# exp21ac.net
KiCad netlist of a schematic drawn in EAGLE
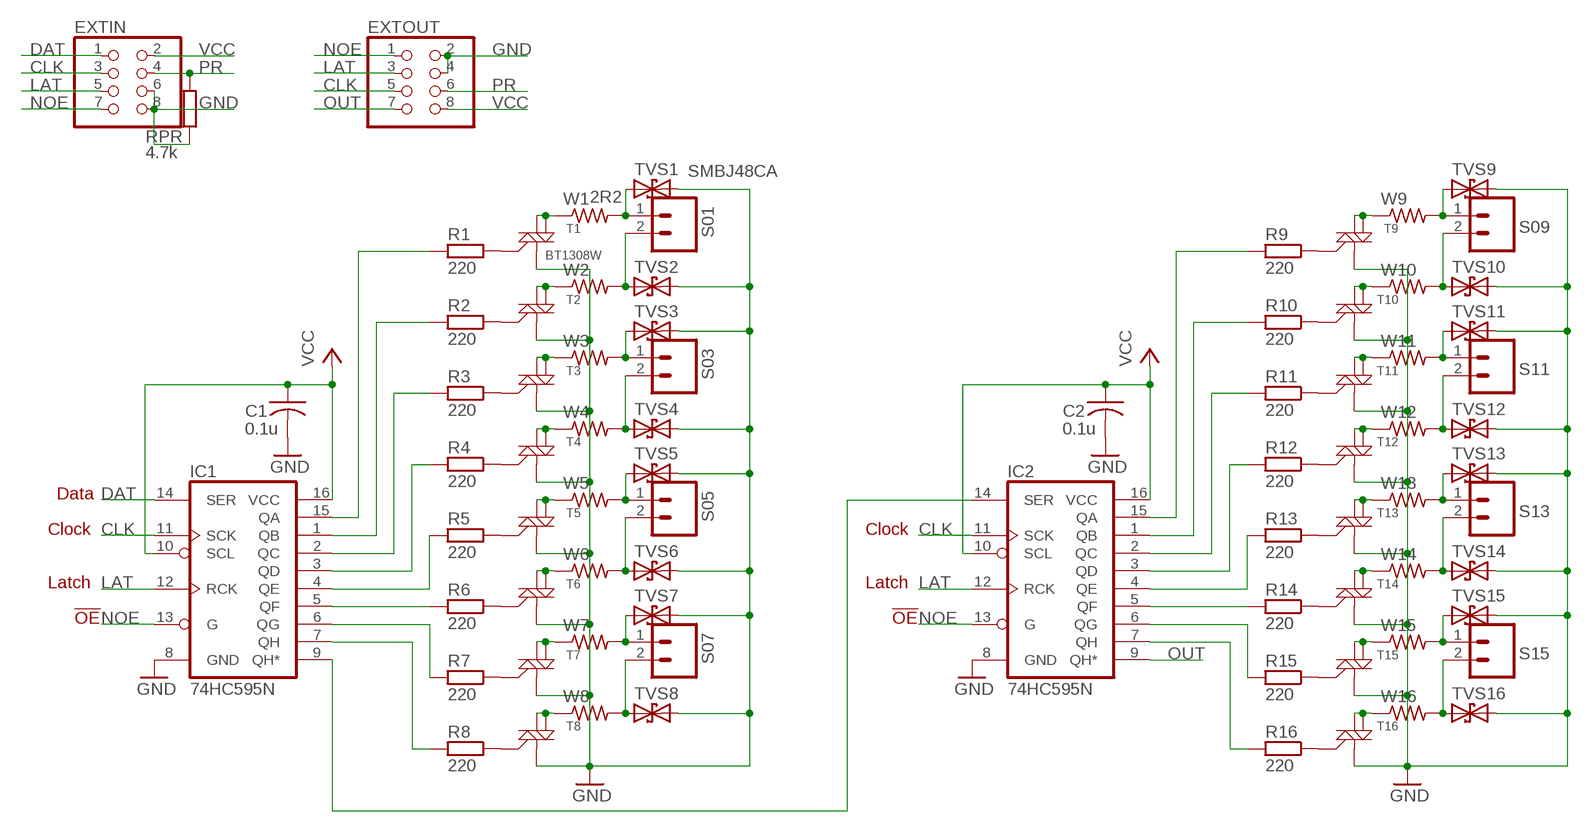
[diagram p0: schematic, sheet 1]

(export (version "E")
  (design (tool "Eeschema 10.0.6"))
  (components
    (comp (ref "C1")
      (value "0.1u")
      (footprint "eagle-import:C0603K")
      (libsource (lib "eagle-import") (part "C-USC0603K"))
    )
    (comp (ref "C2")
      (value "0.1u")
      (footprint "eagle-import:C0603K")
      (libsource (lib "eagle-import") (part "C-USC0603K"))
    )
    (comp (ref "EXTIN")
      (value "PINHD-2X4/90")
      (footprint "eagle-import:2X04_90")
      (libsource (lib "eagle-import") (part "PINHD-2X4/90"))
    )
    (comp (ref "EXTOUT")
      (value "PINHD-2X4/90")
      (footprint "eagle-import:2X04_90")
      (libsource (lib "eagle-import") (part "PINHD-2X4/90"))
    )
    (comp (ref "IC1")
      (value "74HC595N")
      (footprint "eagle-import:SO16")
      (libsource (lib "eagle-import") (part "74595DLS"))
    )
    (comp (ref "IC2")
      (value "74HC595N")
      (footprint "eagle-import:SO16")
      (libsource (lib "eagle-import") (part "74595DLS"))
    )
    (comp (ref "R1")
      (value "220")
      (footprint "eagle-import:R0603")
      (libsource (lib "eagle-import") (part "R-EU_R0603"))
    )
    (comp (ref "R2")
      (value "220")
      (footprint "eagle-import:R0603")
      (libsource (lib "eagle-import") (part "R-EU_R0603"))
    )
    (comp (ref "R3")
      (value "220")
      (footprint "eagle-import:R0603")
      (libsource (lib "eagle-import") (part "R-EU_R0603"))
    )
    (comp (ref "R4")
      (value "220")
      (footprint "eagle-import:R0603")
      (libsource (lib "eagle-import") (part "R-EU_R0603"))
    )
    (comp (ref "R5")
      (value "220")
      (footprint "eagle-import:R0603")
      (libsource (lib "eagle-import") (part "R-EU_R0603"))
    )
    (comp (ref "R6")
      (value "220")
      (footprint "eagle-import:R0603")
      (libsource (lib "eagle-import") (part "R-EU_R0603"))
    )
    (comp (ref "R7")
      (value "220")
      (footprint "eagle-import:R0603")
      (libsource (lib "eagle-import") (part "R-EU_R0603"))
    )
    (comp (ref "R8")
      (value "220")
      (footprint "eagle-import:R0603")
      (libsource (lib "eagle-import") (part "R-EU_R0603"))
    )
    (comp (ref "R9")
      (value "220")
      (footprint "eagle-import:R0603")
      (libsource (lib "eagle-import") (part "R-EU_R0603"))
    )
    (comp (ref "R10")
      (value "220")
      (footprint "eagle-import:R0603")
      (libsource (lib "eagle-import") (part "R-EU_R0603"))
    )
    (comp (ref "R11")
      (value "220")
      (footprint "eagle-import:R0603")
      (libsource (lib "eagle-import") (part "R-EU_R0603"))
    )
    (comp (ref "R12")
      (value "220")
      (footprint "eagle-import:R0603")
      (libsource (lib "eagle-import") (part "R-EU_R0603"))
    )
    (comp (ref "R13")
      (value "220")
      (footprint "eagle-import:R0603")
      (libsource (lib "eagle-import") (part "R-EU_R0603"))
    )
    (comp (ref "R14")
      (value "220")
      (footprint "eagle-import:R0603")
      (libsource (lib "eagle-import") (part "R-EU_R0603"))
    )
    (comp (ref "R15")
      (value "220")
      (footprint "eagle-import:R0603")
      (libsource (lib "eagle-import") (part "R-EU_R0603"))
    )
    (comp (ref "R16")
      (value "220")
      (footprint "eagle-import:R0603")
      (libsource (lib "eagle-import") (part "R-EU_R0603"))
    )
    (comp (ref "RPR")
      (value "4.7k")
      (footprint "eagle-import:R0603")
      (libsource (lib "eagle-import") (part "R-EU_R0603"))
    )
    (comp (ref "S01")
      (value "M025MM-X")
      (footprint "eagle-import:SCREWTERMINAL-5MM-2-X")
      (libsource (lib "eagle-import") (part "M025MM-X"))
    )
    (comp (ref "S03")
      (value "M025MM-X")
      (footprint "eagle-import:SCREWTERMINAL-5MM-2-X")
      (libsource (lib "eagle-import") (part "M025MM-X"))
    )
    (comp (ref "S05")
      (value "M025MM-X")
      (footprint "eagle-import:SCREWTERMINAL-5MM-2-X")
      (libsource (lib "eagle-import") (part "M025MM-X"))
    )
    (comp (ref "S07")
      (value "M025MM-X")
      (footprint "eagle-import:SCREWTERMINAL-5MM-2-X")
      (libsource (lib "eagle-import") (part "M025MM-X"))
    )
    (comp (ref "S09")
      (value "M025MM-X")
      (footprint "eagle-import:SCREWTERMINAL-5MM-2-X")
      (libsource (lib "eagle-import") (part "M025MM-X"))
    )
    (comp (ref "S11")
      (value "M025MM-X")
      (footprint "eagle-import:SCREWTERMINAL-5MM-2-X")
      (libsource (lib "eagle-import") (part "M025MM-X"))
    )
    (comp (ref "S13")
      (value "M025MM-X")
      (footprint "eagle-import:SCREWTERMINAL-5MM-2-X")
      (libsource (lib "eagle-import") (part "M025MM-X"))
    )
    (comp (ref "S15")
      (value "M025MM-X")
      (footprint "eagle-import:SCREWTERMINAL-5MM-2-X")
      (libsource (lib "eagle-import") (part "M025MM-X"))
    )
    (comp (ref "T1")
      (value "BT1308W")
      (footprint "eagle-import:SOT223")
      (libsource (lib "eagle-import") (part "MAC97SOT223"))
    )
    (comp (ref "T2")
      (value "MAC97SOT223")
      (footprint "eagle-import:SOT223")
      (libsource (lib "eagle-import") (part "MAC97SOT223"))
    )
    (comp (ref "T3")
      (value "MAC97SOT223")
      (footprint "eagle-import:SOT223")
      (libsource (lib "eagle-import") (part "MAC97SOT223"))
    )
    (comp (ref "T4")
      (value "MAC97SOT223")
      (footprint "eagle-import:SOT223")
      (libsource (lib "eagle-import") (part "MAC97SOT223"))
    )
    (comp (ref "T5")
      (value "MAC97SOT223")
      (footprint "eagle-import:SOT223")
      (libsource (lib "eagle-import") (part "MAC97SOT223"))
    )
    (comp (ref "T6")
      (value "MAC97SOT223")
      (footprint "eagle-import:SOT223")
      (libsource (lib "eagle-import") (part "MAC97SOT223"))
    )
    (comp (ref "T7")
      (value "MAC97SOT223")
      (footprint "eagle-import:SOT223")
      (libsource (lib "eagle-import") (part "MAC97SOT223"))
    )
    (comp (ref "T8")
      (value "MAC97SOT223")
      (footprint "eagle-import:SOT223")
      (libsource (lib "eagle-import") (part "MAC97SOT223"))
    )
    (comp (ref "T9")
      (value "MAC97")
      (footprint "eagle-import:SOT223")
      (libsource (lib "eagle-import") (part "MAC97SOT223"))
    )
    (comp (ref "T10")
      (value "MAC97")
      (footprint "eagle-import:SOT223")
      (libsource (lib "eagle-import") (part "MAC97SOT223"))
    )
    (comp (ref "T11")
      (value "MAC97")
      (footprint "eagle-import:SOT223")
      (libsource (lib "eagle-import") (part "MAC97SOT223"))
    )
    (comp (ref "T12")
      (value "MAC97")
      (footprint "eagle-import:SOT223")
      (libsource (lib "eagle-import") (part "MAC97SOT223"))
    )
    (comp (ref "T13")
      (value "MAC97")
      (footprint "eagle-import:SOT223")
      (libsource (lib "eagle-import") (part "MAC97SOT223"))
    )
    (comp (ref "T14")
      (value "MAC97")
      (footprint "eagle-import:SOT223")
      (libsource (lib "eagle-import") (part "MAC97SOT223"))
    )
    (comp (ref "T15")
      (value "MAC97")
      (footprint "eagle-import:SOT223")
      (libsource (lib "eagle-import") (part "MAC97SOT223"))
    )
    (comp (ref "T16")
      (value "MAC97")
      (footprint "eagle-import:SOT223")
      (libsource (lib "eagle-import") (part "MAC97SOT223"))
    )
    (comp (ref "TVS1")
      (value "SMBJ48CA")
      (footprint "eagle-import:SMB")
      (libsource (lib "eagle-import") (part "TVSSMB"))
    )
    (comp (ref "TVS2")
      (value "TVSSMB")
      (footprint "eagle-import:SMB")
      (libsource (lib "eagle-import") (part "TVSSMB"))
    )
    (comp (ref "TVS3")
      (value "TVSSMB")
      (footprint "eagle-import:SMB")
      (libsource (lib "eagle-import") (part "TVSSMB"))
    )
    (comp (ref "TVS4")
      (value "TVSSMB")
      (footprint "eagle-import:SMB")
      (libsource (lib "eagle-import") (part "TVSSMB"))
    )
    (comp (ref "TVS5")
      (value "TVSSMB")
      (footprint "eagle-import:SMB")
      (libsource (lib "eagle-import") (part "TVSSMB"))
    )
    (comp (ref "TVS6")
      (value "TVSSMB")
      (footprint "eagle-import:SMB")
      (libsource (lib "eagle-import") (part "TVSSMB"))
    )
    (comp (ref "TVS7")
      (value "TVSSMB")
      (footprint "eagle-import:SMB")
      (libsource (lib "eagle-import") (part "TVSSMB"))
    )
    (comp (ref "TVS8")
      (value "TVSSMB")
      (footprint "eagle-import:SMB")
      (libsource (lib "eagle-import") (part "TVSSMB"))
    )
    (comp (ref "TVS9")
      (value "TVSSMB")
      (footprint "eagle-import:SMB")
      (libsource (lib "eagle-import") (part "TVSSMB"))
    )
    (comp (ref "TVS10")
      (value "TVSSMB")
      (footprint "eagle-import:SMB")
      (libsource (lib "eagle-import") (part "TVSSMB"))
    )
    (comp (ref "TVS11")
      (value "TVSSMB")
      (footprint "eagle-import:SMB")
      (libsource (lib "eagle-import") (part "TVSSMB"))
    )
    (comp (ref "TVS12")
      (value "TVSSMB")
      (footprint "eagle-import:SMB")
      (libsource (lib "eagle-import") (part "TVSSMB"))
    )
    (comp (ref "TVS13")
      (value "TVSSMB")
      (footprint "eagle-import:SMB")
      (libsource (lib "eagle-import") (part "TVSSMB"))
    )
    (comp (ref "TVS14")
      (value "TVSSMB")
      (footprint "eagle-import:SMB")
      (libsource (lib "eagle-import") (part "TVSSMB"))
    )
    (comp (ref "TVS15")
      (value "TVSSMB")
      (footprint "eagle-import:SMB")
      (libsource (lib "eagle-import") (part "TVSSMB"))
    )
    (comp (ref "TVS16")
      (value "TVSSMB")
      (footprint "eagle-import:SMB")
      (libsource (lib "eagle-import") (part "TVSSMB"))
    )
    (comp (ref "W1")
      (value "2R2")
      (footprint "eagle-import:R2512")
      (libsource (lib "eagle-import") (part "R-US_R2512"))
    )
    (comp (ref "W2")
      (value "R-US_R2512")
      (footprint "eagle-import:R2512")
      (libsource (lib "eagle-import") (part "R-US_R2512"))
    )
    (comp (ref "W3")
      (value "R-US_R2512")
      (footprint "eagle-import:R2512")
      (libsource (lib "eagle-import") (part "R-US_R2512"))
    )
    (comp (ref "W4")
      (value "R-US_R2512")
      (footprint "eagle-import:R2512")
      (libsource (lib "eagle-import") (part "R-US_R2512"))
    )
    (comp (ref "W5")
      (value "R-US_R2512")
      (footprint "eagle-import:R2512")
      (libsource (lib "eagle-import") (part "R-US_R2512"))
    )
    (comp (ref "W6")
      (value "R-US_R2512")
      (footprint "eagle-import:R2512")
      (libsource (lib "eagle-import") (part "R-US_R2512"))
    )
    (comp (ref "W7")
      (value "R-US_R2512")
      (footprint "eagle-import:R2512")
      (libsource (lib "eagle-import") (part "R-US_R2512"))
    )
    (comp (ref "W8")
      (value "R-US_R2512")
      (footprint "eagle-import:R2512")
      (libsource (lib "eagle-import") (part "R-US_R2512"))
    )
    (comp (ref "W9")
      (value "R-US_R2512")
      (footprint "eagle-import:R2512")
      (libsource (lib "eagle-import") (part "R-US_R2512"))
    )
    (comp (ref "W10")
      (value "R-US_R2512")
      (footprint "eagle-import:R2512")
      (libsource (lib "eagle-import") (part "R-US_R2512"))
    )
    (comp (ref "W11")
      (value "R-US_R2512")
      (footprint "eagle-import:R2512")
      (libsource (lib "eagle-import") (part "R-US_R2512"))
    )
    (comp (ref "W12")
      (value "R-US_R2512")
      (footprint "eagle-import:R2512")
      (libsource (lib "eagle-import") (part "R-US_R2512"))
    )
    (comp (ref "W13")
      (value "R-US_R2512")
      (footprint "eagle-import:R2512")
      (libsource (lib "eagle-import") (part "R-US_R2512"))
    )
    (comp (ref "W14")
      (value "R-US_R2512")
      (footprint "eagle-import:R2512")
      (libsource (lib "eagle-import") (part "R-US_R2512"))
    )
    (comp (ref "W15")
      (value "R-US_R2512")
      (footprint "eagle-import:R2512")
      (libsource (lib "eagle-import") (part "R-US_R2512"))
    )
    (comp (ref "W16")
      (value "R-US_R2512")
      (footprint "eagle-import:R2512")
      (libsource (lib "eagle-import") (part "R-US_R2512"))
    )
  )
  (nets
    (net (code "1") (name "/CLK") (class "Default")
      (node (ref "EXTIN") (pin "3") (pinfunction "3_3") (pintype "passive"))
      (node (ref "EXTOUT") (pin "5") (pinfunction "5_5") (pintype "passive"))
      (node (ref "IC1") (pin "11") (pinfunction "SCK_11") (pintype "input"))
      (node (ref "IC2") (pin "11") (pinfunction "SCK_11") (pintype "input"))
    )
    (net (code "2") (name "/DAT") (class "Default")
      (node (ref "EXTIN") (pin "1") (pinfunction "1_1") (pintype "passive"))
      (node (ref "IC1") (pin "14") (pinfunction "SER_14") (pintype "input"))
    )
    (net (code "3") (name "/LAT") (class "Default")
      (node (ref "EXTIN") (pin "5") (pinfunction "5_5") (pintype "passive"))
      (node (ref "EXTOUT") (pin "3") (pinfunction "3_3") (pintype "passive"))
      (node (ref "IC1") (pin "12") (pinfunction "RCK_12") (pintype "input"))
      (node (ref "IC2") (pin "12") (pinfunction "RCK_12") (pintype "input"))
    )
    (net (code "4") (name "/NOE") (class "Default")
      (node (ref "EXTIN") (pin "7") (pinfunction "7_7") (pintype "passive"))
      (node (ref "EXTOUT") (pin "1") (pinfunction "1_1") (pintype "passive"))
      (node (ref "IC1") (pin "13") (pinfunction "G_13") (pintype "input"))
      (node (ref "IC2") (pin "13") (pinfunction "G_13") (pintype "input"))
    )
    (net (code "5") (name "/OUT") (class "Default")
      (node (ref "EXTOUT") (pin "7") (pinfunction "7_7") (pintype "passive"))
      (node (ref "IC2") (pin "9") (pinfunction "QH*_9") (pintype "tri_state"))
    )
    (net (code "6") (name "/PR") (class "Default")
      (node (ref "EXTIN") (pin "4") (pinfunction "4_4") (pintype "passive"))
      (node (ref "EXTOUT") (pin "6") (pinfunction "6_6") (pintype "passive"))
      (node (ref "RPR") (pin "2") (pinfunction "2_2") (pintype "passive"))
    )
    (net (code "7") (name "GND") (class "Default")
      (node (ref "C1") (pin "2") (pinfunction "2_2") (pintype "passive"))
      (node (ref "C2") (pin "2") (pinfunction "2_2") (pintype "passive"))
      (node (ref "EXTIN") (pin "6") (pinfunction "6_6") (pintype "passive"))
      (node (ref "EXTIN") (pin "8") (pinfunction "8_8") (pintype "passive"))
      (node (ref "EXTOUT") (pin "2") (pinfunction "2_2") (pintype "passive"))
      (node (ref "EXTOUT") (pin "4") (pinfunction "4_4") (pintype "passive"))
      (node (ref "IC1") (pin "8") (pinfunction "GND_8") (pintype "power_in"))
      (node (ref "IC2") (pin "8") (pinfunction "GND_8") (pintype "power_in"))
      (node (ref "RPR") (pin "1") (pinfunction "1_1") (pintype "passive"))
      (node (ref "T1") (pin "1") (pinfunction "M1_1") (pintype "bidirectional"))
      (node (ref "T10") (pin "1") (pinfunction "M1_1") (pintype "bidirectional"))
      (node (ref "T11") (pin "1") (pinfunction "M1_1") (pintype "bidirectional"))
      (node (ref "T12") (pin "1") (pinfunction "M1_1") (pintype "bidirectional"))
      (node (ref "T13") (pin "1") (pinfunction "M1_1") (pintype "bidirectional"))
      (node (ref "T14") (pin "1") (pinfunction "M1_1") (pintype "bidirectional"))
      (node (ref "T15") (pin "1") (pinfunction "M1_1") (pintype "bidirectional"))
      (node (ref "T16") (pin "1") (pinfunction "M1_1") (pintype "bidirectional"))
      (node (ref "T2") (pin "1") (pinfunction "M1_1") (pintype "bidirectional"))
      (node (ref "T3") (pin "1") (pinfunction "M1_1") (pintype "bidirectional"))
      (node (ref "T4") (pin "1") (pinfunction "M1_1") (pintype "bidirectional"))
      (node (ref "T5") (pin "1") (pinfunction "M1_1") (pintype "bidirectional"))
      (node (ref "T6") (pin "1") (pinfunction "M1_1") (pintype "bidirectional"))
      (node (ref "T7") (pin "1") (pinfunction "M1_1") (pintype "bidirectional"))
      (node (ref "T8") (pin "1") (pinfunction "M1_1") (pintype "bidirectional"))
      (node (ref "T9") (pin "1") (pinfunction "M1_1") (pintype "bidirectional"))
      (node (ref "TVS1") (pin "C") (pinfunction "2_C") (pintype "passive"))
      (node (ref "TVS10") (pin "C") (pinfunction "2_C") (pintype "passive"))
      (node (ref "TVS11") (pin "C") (pinfunction "2_C") (pintype "passive"))
      (node (ref "TVS12") (pin "C") (pinfunction "2_C") (pintype "passive"))
      (node (ref "TVS13") (pin "C") (pinfunction "2_C") (pintype "passive"))
      (node (ref "TVS14") (pin "C") (pinfunction "2_C") (pintype "passive"))
      (node (ref "TVS15") (pin "C") (pinfunction "2_C") (pintype "passive"))
      (node (ref "TVS16") (pin "C") (pinfunction "2_C") (pintype "passive"))
      (node (ref "TVS2") (pin "C") (pinfunction "2_C") (pintype "passive"))
      (node (ref "TVS3") (pin "C") (pinfunction "2_C") (pintype "passive"))
      (node (ref "TVS4") (pin "C") (pinfunction "2_C") (pintype "passive"))
      (node (ref "TVS5") (pin "C") (pinfunction "2_C") (pintype "passive"))
      (node (ref "TVS6") (pin "C") (pinfunction "2_C") (pintype "passive"))
      (node (ref "TVS7") (pin "C") (pinfunction "2_C") (pintype "passive"))
      (node (ref "TVS8") (pin "C") (pinfunction "2_C") (pintype "passive"))
      (node (ref "TVS9") (pin "C") (pinfunction "2_C") (pintype "passive"))
    )
    (net (code "8") (name "Net-(IC1-QA)") (class "Default")
      (node (ref "IC1") (pin "15") (pinfunction "QA_15") (pintype "tri_state"))
      (node (ref "R1") (pin "2") (pinfunction "2_2") (pintype "passive"))
    )
    (net (code "9") (name "Net-(IC1-QB)") (class "Default")
      (node (ref "IC1") (pin "1") (pinfunction "QB_1") (pintype "tri_state"))
      (node (ref "R2") (pin "2") (pinfunction "2_2") (pintype "passive"))
    )
    (net (code "10") (name "Net-(IC1-QC)") (class "Default")
      (node (ref "IC1") (pin "2") (pinfunction "QC_2") (pintype "tri_state"))
      (node (ref "R3") (pin "2") (pinfunction "2_2") (pintype "passive"))
    )
    (net (code "11") (name "Net-(IC1-QD)") (class "Default")
      (node (ref "IC1") (pin "3") (pinfunction "QD_3") (pintype "tri_state"))
      (node (ref "R4") (pin "2") (pinfunction "2_2") (pintype "passive"))
    )
    (net (code "12") (name "Net-(IC1-QE)") (class "Default")
      (node (ref "IC1") (pin "4") (pinfunction "QE_4") (pintype "tri_state"))
      (node (ref "R5") (pin "2") (pinfunction "2_2") (pintype "passive"))
    )
    (net (code "13") (name "Net-(IC1-QF)") (class "Default")
      (node (ref "IC1") (pin "5") (pinfunction "QF_5") (pintype "tri_state"))
      (node (ref "R6") (pin "2") (pinfunction "2_2") (pintype "passive"))
    )
    (net (code "14") (name "Net-(IC1-QG)") (class "Default")
      (node (ref "IC1") (pin "6") (pinfunction "QG_6") (pintype "tri_state"))
      (node (ref "R7") (pin "2") (pinfunction "2_2") (pintype "passive"))
    )
    (net (code "15") (name "Net-(IC1-QH)") (class "Default")
      (node (ref "IC1") (pin "7") (pinfunction "QH_7") (pintype "tri_state"))
      (node (ref "R8") (pin "2") (pinfunction "2_2") (pintype "passive"))
    )
    (net (code "16") (name "Net-(IC1-QH*)") (class "Default")
      (node (ref "IC1") (pin "9") (pinfunction "QH*_9") (pintype "tri_state"))
      (node (ref "IC2") (pin "14") (pinfunction "SER_14") (pintype "input"))
    )
    (net (code "17") (name "Net-(IC2-QA)") (class "Default")
      (node (ref "IC2") (pin "15") (pinfunction "QA_15") (pintype "tri_state"))
      (node (ref "R9") (pin "2") (pinfunction "2_2") (pintype "passive"))
    )
    (net (code "18") (name "Net-(IC2-QB)") (class "Default")
      (node (ref "IC2") (pin "1") (pinfunction "QB_1") (pintype "tri_state"))
      (node (ref "R10") (pin "2") (pinfunction "2_2") (pintype "passive"))
    )
    (net (code "19") (name "Net-(IC2-QC)") (class "Default")
      (node (ref "IC2") (pin "2") (pinfunction "QC_2") (pintype "tri_state"))
      (node (ref "R11") (pin "2") (pinfunction "2_2") (pintype "passive"))
    )
    (net (code "20") (name "Net-(IC2-QD)") (class "Default")
      (node (ref "IC2") (pin "3") (pinfunction "QD_3") (pintype "tri_state"))
      (node (ref "R12") (pin "2") (pinfunction "2_2") (pintype "passive"))
    )
    (net (code "21") (name "Net-(IC2-QE)") (class "Default")
      (node (ref "IC2") (pin "4") (pinfunction "QE_4") (pintype "tri_state"))
      (node (ref "R13") (pin "2") (pinfunction "2_2") (pintype "passive"))
    )
    (net (code "22") (name "Net-(IC2-QF)") (class "Default")
      (node (ref "IC2") (pin "5") (pinfunction "QF_5") (pintype "tri_state"))
      (node (ref "R14") (pin "2") (pinfunction "2_2") (pintype "passive"))
    )
    (net (code "23") (name "Net-(IC2-QG)") (class "Default")
      (node (ref "IC2") (pin "6") (pinfunction "QG_6") (pintype "tri_state"))
      (node (ref "R15") (pin "2") (pinfunction "2_2") (pintype "passive"))
    )
    (net (code "24") (name "Net-(IC2-QH)") (class "Default")
      (node (ref "IC2") (pin "7") (pinfunction "QH_7") (pintype "tri_state"))
      (node (ref "R16") (pin "2") (pinfunction "2_2") (pintype "passive"))
    )
    (net (code "25") (name "Net-(T1-G)") (class "Default")
      (node (ref "R1") (pin "1") (pinfunction "1_1") (pintype "passive"))
      (node (ref "T1") (pin "3") (pinfunction "G_3") (pintype "bidirectional"))
    )
    (net (code "26") (name "Net-(T1-M2)") (class "Default")
      (node (ref "T1") (pin "2") (pinfunction "M2_2") (pintype "bidirectional"))
      (node (ref "T1") (pin "4") (pinfunction "M2-4_4") (pintype "bidirectional"))
      (node (ref "W1") (pin "1") (pinfunction "1_1") (pintype "passive"))
    )
    (net (code "27") (name "Net-(T2-G)") (class "Default")
      (node (ref "R2") (pin "1") (pinfunction "1_1") (pintype "passive"))
      (node (ref "T2") (pin "3") (pinfunction "G_3") (pintype "bidirectional"))
    )
    (net (code "28") (name "Net-(T2-M2)") (class "Default")
      (node (ref "T2") (pin "2") (pinfunction "M2_2") (pintype "bidirectional"))
      (node (ref "T2") (pin "4") (pinfunction "M2-4_4") (pintype "bidirectional"))
      (node (ref "W2") (pin "1") (pinfunction "1_1") (pintype "passive"))
    )
    (net (code "29") (name "Net-(T3-G)") (class "Default")
      (node (ref "R3") (pin "1") (pinfunction "1_1") (pintype "passive"))
      (node (ref "T3") (pin "3") (pinfunction "G_3") (pintype "bidirectional"))
    )
    (net (code "30") (name "Net-(T3-M2)") (class "Default")
      (node (ref "T3") (pin "2") (pinfunction "M2_2") (pintype "bidirectional"))
      (node (ref "T3") (pin "4") (pinfunction "M2-4_4") (pintype "bidirectional"))
      (node (ref "W3") (pin "1") (pinfunction "1_1") (pintype "passive"))
    )
    (net (code "31") (name "Net-(T4-G)") (class "Default")
      (node (ref "R4") (pin "1") (pinfunction "1_1") (pintype "passive"))
      (node (ref "T4") (pin "3") (pinfunction "G_3") (pintype "bidirectional"))
    )
    (net (code "32") (name "Net-(T4-M2)") (class "Default")
      (node (ref "T4") (pin "2") (pinfunction "M2_2") (pintype "bidirectional"))
      (node (ref "T4") (pin "4") (pinfunction "M2-4_4") (pintype "bidirectional"))
      (node (ref "W4") (pin "1") (pinfunction "1_1") (pintype "passive"))
    )
    (net (code "33") (name "Net-(T5-G)") (class "Default")
      (node (ref "R5") (pin "1") (pinfunction "1_1") (pintype "passive"))
      (node (ref "T5") (pin "3") (pinfunction "G_3") (pintype "bidirectional"))
    )
    (net (code "34") (name "Net-(T5-M2)") (class "Default")
      (node (ref "T5") (pin "2") (pinfunction "M2_2") (pintype "bidirectional"))
      (node (ref "T5") (pin "4") (pinfunction "M2-4_4") (pintype "bidirectional"))
      (node (ref "W5") (pin "1") (pinfunction "1_1") (pintype "passive"))
    )
    (net (code "35") (name "Net-(T6-G)") (class "Default")
      (node (ref "R6") (pin "1") (pinfunction "1_1") (pintype "passive"))
      (node (ref "T6") (pin "3") (pinfunction "G_3") (pintype "bidirectional"))
    )
    (net (code "36") (name "Net-(T6-M2)") (class "Default")
      (node (ref "T6") (pin "2") (pinfunction "M2_2") (pintype "bidirectional"))
      (node (ref "T6") (pin "4") (pinfunction "M2-4_4") (pintype "bidirectional"))
      (node (ref "W6") (pin "1") (pinfunction "1_1") (pintype "passive"))
    )
    (net (code "37") (name "Net-(T7-G)") (class "Default")
      (node (ref "R7") (pin "1") (pinfunction "1_1") (pintype "passive"))
      (node (ref "T7") (pin "3") (pinfunction "G_3") (pintype "bidirectional"))
    )
    (net (code "38") (name "Net-(T7-M2)") (class "Default")
      (node (ref "T7") (pin "2") (pinfunction "M2_2") (pintype "bidirectional"))
      (node (ref "T7") (pin "4") (pinfunction "M2-4_4") (pintype "bidirectional"))
      (node (ref "W7") (pin "1") (pinfunction "1_1") (pintype "passive"))
    )
    (net (code "39") (name "Net-(T8-G)") (class "Default")
      (node (ref "R8") (pin "1") (pinfunction "1_1") (pintype "passive"))
      (node (ref "T8") (pin "3") (pinfunction "G_3") (pintype "bidirectional"))
    )
    (net (code "40") (name "Net-(T8-M2)") (class "Default")
      (node (ref "T8") (pin "2") (pinfunction "M2_2") (pintype "bidirectional"))
      (node (ref "T8") (pin "4") (pinfunction "M2-4_4") (pintype "bidirectional"))
      (node (ref "W8") (pin "1") (pinfunction "1_1") (pintype "passive"))
    )
    (net (code "41") (name "Net-(T9-G)") (class "Default")
      (node (ref "R9") (pin "1") (pinfunction "1_1") (pintype "passive"))
      (node (ref "T9") (pin "3") (pinfunction "G_3") (pintype "bidirectional"))
    )
    (net (code "42") (name "Net-(T9-M2)") (class "Default")
      (node (ref "T9") (pin "2") (pinfunction "M2_2") (pintype "bidirectional"))
      (node (ref "T9") (pin "4") (pinfunction "M2-4_4") (pintype "bidirectional"))
      (node (ref "W9") (pin "1") (pinfunction "1_1") (pintype "passive"))
    )
    (net (code "43") (name "Net-(T10-G)") (class "Default")
      (node (ref "R10") (pin "1") (pinfunction "1_1") (pintype "passive"))
      (node (ref "T10") (pin "3") (pinfunction "G_3") (pintype "bidirectional"))
    )
    (net (code "44") (name "Net-(T10-M2)") (class "Default")
      (node (ref "T10") (pin "2") (pinfunction "M2_2") (pintype "bidirectional"))
      (node (ref "T10") (pin "4") (pinfunction "M2-4_4") (pintype "bidirectional"))
      (node (ref "W10") (pin "1") (pinfunction "1_1") (pintype "passive"))
    )
    (net (code "45") (name "Net-(T11-G)") (class "Default")
      (node (ref "R11") (pin "1") (pinfunction "1_1") (pintype "passive"))
      (node (ref "T11") (pin "3") (pinfunction "G_3") (pintype "bidirectional"))
    )
    (net (code "46") (name "Net-(T11-M2)") (class "Default")
      (node (ref "T11") (pin "2") (pinfunction "M2_2") (pintype "bidirectional"))
      (node (ref "T11") (pin "4") (pinfunction "M2-4_4") (pintype "bidirectional"))
      (node (ref "W11") (pin "1") (pinfunction "1_1") (pintype "passive"))
    )
    (net (code "47") (name "Net-(T12-G)") (class "Default")
      (node (ref "R12") (pin "1") (pinfunction "1_1") (pintype "passive"))
      (node (ref "T12") (pin "3") (pinfunction "G_3") (pintype "bidirectional"))
    )
    (net (code "48") (name "Net-(T12-M2)") (class "Default")
      (node (ref "T12") (pin "2") (pinfunction "M2_2") (pintype "bidirectional"))
      (node (ref "T12") (pin "4") (pinfunction "M2-4_4") (pintype "bidirectional"))
      (node (ref "W12") (pin "1") (pinfunction "1_1") (pintype "passive"))
    )
    (net (code "49") (name "Net-(T13-G)") (class "Default")
      (node (ref "R13") (pin "1") (pinfunction "1_1") (pintype "passive"))
      (node (ref "T13") (pin "3") (pinfunction "G_3") (pintype "bidirectional"))
    )
    (net (code "50") (name "Net-(T13-M2)") (class "Default")
      (node (ref "T13") (pin "2") (pinfunction "M2_2") (pintype "bidirectional"))
      (node (ref "T13") (pin "4") (pinfunction "M2-4_4") (pintype "bidirectional"))
      (node (ref "W13") (pin "1") (pinfunction "1_1") (pintype "passive"))
    )
    (net (code "51") (name "Net-(T14-G)") (class "Default")
      (node (ref "R14") (pin "1") (pinfunction "1_1") (pintype "passive"))
      (node (ref "T14") (pin "3") (pinfunction "G_3") (pintype "bidirectional"))
    )
    (net (code "52") (name "Net-(T14-M2)") (class "Default")
      (node (ref "T14") (pin "2") (pinfunction "M2_2") (pintype "bidirectional"))
      (node (ref "T14") (pin "4") (pinfunction "M2-4_4") (pintype "bidirectional"))
      (node (ref "W14") (pin "1") (pinfunction "1_1") (pintype "passive"))
    )
    (net (code "53") (name "Net-(T15-G)") (class "Default")
      (node (ref "R15") (pin "1") (pinfunction "1_1") (pintype "passive"))
      (node (ref "T15") (pin "3") (pinfunction "G_3") (pintype "bidirectional"))
    )
    (net (code "54") (name "Net-(T15-M2)") (class "Default")
      (node (ref "T15") (pin "2") (pinfunction "M2_2") (pintype "bidirectional"))
      (node (ref "T15") (pin "4") (pinfunction "M2-4_4") (pintype "bidirectional"))
      (node (ref "W15") (pin "1") (pinfunction "1_1") (pintype "passive"))
    )
    (net (code "55") (name "Net-(T16-G)") (class "Default")
      (node (ref "R16") (pin "1") (pinfunction "1_1") (pintype "passive"))
      (node (ref "T16") (pin "3") (pinfunction "G_3") (pintype "bidirectional"))
    )
    (net (code "56") (name "Net-(T16-M2)") (class "Default")
      (node (ref "T16") (pin "2") (pinfunction "M2_2") (pintype "bidirectional"))
      (node (ref "T16") (pin "4") (pinfunction "M2-4_4") (pintype "bidirectional"))
      (node (ref "W16") (pin "1") (pinfunction "1_1") (pintype "passive"))
    )
    (net (code "57") (name "Net-(TVS1-1)") (class "Default")
      (node (ref "S01") (pin "1") (pinfunction "1_1") (pintype "passive"))
      (node (ref "TVS1") (pin "A") (pinfunction "1_A") (pintype "passive"))
      (node (ref "W1") (pin "2") (pinfunction "2_2") (pintype "passive"))
    )
    (net (code "58") (name "Net-(TVS2-1)") (class "Default")
      (node (ref "S01") (pin "2") (pinfunction "2_2") (pintype "passive"))
      (node (ref "TVS2") (pin "A") (pinfunction "1_A") (pintype "passive"))
      (node (ref "W2") (pin "2") (pinfunction "2_2") (pintype "passive"))
    )
    (net (code "59") (name "Net-(TVS3-1)") (class "Default")
      (node (ref "S03") (pin "1") (pinfunction "1_1") (pintype "passive"))
      (node (ref "TVS3") (pin "A") (pinfunction "1_A") (pintype "passive"))
      (node (ref "W3") (pin "2") (pinfunction "2_2") (pintype "passive"))
    )
    (net (code "60") (name "Net-(TVS4-1)") (class "Default")
      (node (ref "S03") (pin "2") (pinfunction "2_2") (pintype "passive"))
      (node (ref "TVS4") (pin "A") (pinfunction "1_A") (pintype "passive"))
      (node (ref "W4") (pin "2") (pinfunction "2_2") (pintype "passive"))
    )
    (net (code "61") (name "Net-(TVS5-1)") (class "Default")
      (node (ref "S05") (pin "1") (pinfunction "1_1") (pintype "passive"))
      (node (ref "TVS5") (pin "A") (pinfunction "1_A") (pintype "passive"))
      (node (ref "W5") (pin "2") (pinfunction "2_2") (pintype "passive"))
    )
    (net (code "62") (name "Net-(TVS6-1)") (class "Default")
      (node (ref "S05") (pin "2") (pinfunction "2_2") (pintype "passive"))
      (node (ref "TVS6") (pin "A") (pinfunction "1_A") (pintype "passive"))
      (node (ref "W6") (pin "2") (pinfunction "2_2") (pintype "passive"))
    )
    (net (code "63") (name "Net-(TVS7-1)") (class "Default")
      (node (ref "S07") (pin "1") (pinfunction "1_1") (pintype "passive"))
      (node (ref "TVS7") (pin "A") (pinfunction "1_A") (pintype "passive"))
      (node (ref "W7") (pin "2") (pinfunction "2_2") (pintype "passive"))
    )
    (net (code "64") (name "Net-(TVS8-1)") (class "Default")
      (node (ref "S07") (pin "2") (pinfunction "2_2") (pintype "passive"))
      (node (ref "TVS8") (pin "A") (pinfunction "1_A") (pintype "passive"))
      (node (ref "W8") (pin "2") (pinfunction "2_2") (pintype "passive"))
    )
    (net (code "65") (name "Net-(TVS9-1)") (class "Default")
      (node (ref "S09") (pin "1") (pinfunction "1_1") (pintype "passive"))
      (node (ref "TVS9") (pin "A") (pinfunction "1_A") (pintype "passive"))
      (node (ref "W9") (pin "2") (pinfunction "2_2") (pintype "passive"))
    )
    (net (code "66") (name "Net-(TVS10-1)") (class "Default")
      (node (ref "S09") (pin "2") (pinfunction "2_2") (pintype "passive"))
      (node (ref "TVS10") (pin "A") (pinfunction "1_A") (pintype "passive"))
      (node (ref "W10") (pin "2") (pinfunction "2_2") (pintype "passive"))
    )
    (net (code "67") (name "Net-(TVS11-1)") (class "Default")
      (node (ref "S11") (pin "1") (pinfunction "1_1") (pintype "passive"))
      (node (ref "TVS11") (pin "A") (pinfunction "1_A") (pintype "passive"))
      (node (ref "W11") (pin "2") (pinfunction "2_2") (pintype "passive"))
    )
    (net (code "68") (name "Net-(TVS12-1)") (class "Default")
      (node (ref "S11") (pin "2") (pinfunction "2_2") (pintype "passive"))
      (node (ref "TVS12") (pin "A") (pinfunction "1_A") (pintype "passive"))
      (node (ref "W12") (pin "2") (pinfunction "2_2") (pintype "passive"))
    )
    (net (code "69") (name "Net-(TVS13-1)") (class "Default")
      (node (ref "S13") (pin "1") (pinfunction "1_1") (pintype "passive"))
      (node (ref "TVS13") (pin "A") (pinfunction "1_A") (pintype "passive"))
      (node (ref "W13") (pin "2") (pinfunction "2_2") (pintype "passive"))
    )
    (net (code "70") (name "Net-(TVS14-1)") (class "Default")
      (node (ref "S13") (pin "2") (pinfunction "2_2") (pintype "passive"))
      (node (ref "TVS14") (pin "A") (pinfunction "1_A") (pintype "passive"))
      (node (ref "W14") (pin "2") (pinfunction "2_2") (pintype "passive"))
    )
    (net (code "71") (name "Net-(TVS15-1)") (class "Default")
      (node (ref "S15") (pin "1") (pinfunction "1_1") (pintype "passive"))
      (node (ref "TVS15") (pin "A") (pinfunction "1_A") (pintype "passive"))
      (node (ref "W15") (pin "2") (pinfunction "2_2") (pintype "passive"))
    )
    (net (code "72") (name "Net-(TVS16-1)") (class "Default")
      (node (ref "S15") (pin "2") (pinfunction "2_2") (pintype "passive"))
      (node (ref "TVS16") (pin "A") (pinfunction "1_A") (pintype "passive"))
      (node (ref "W16") (pin "2") (pinfunction "2_2") (pintype "passive"))
    )
    (net (code "73") (name "VCC") (class "Default")
      (node (ref "C1") (pin "1") (pinfunction "1_1") (pintype "passive"))
      (node (ref "C2") (pin "1") (pinfunction "1_1") (pintype "passive"))
      (node (ref "EXTIN") (pin "2") (pinfunction "2_2") (pintype "passive"))
      (node (ref "EXTOUT") (pin "8") (pinfunction "8_8") (pintype "passive"))
      (node (ref "IC1") (pin "10") (pinfunction "SCL_10") (pintype "input"))
      (node (ref "IC1") (pin "16") (pinfunction "VCC_16") (pintype "power_in"))
      (node (ref "IC2") (pin "10") (pinfunction "SCL_10") (pintype "input"))
      (node (ref "IC2") (pin "16") (pinfunction "VCC_16") (pintype "power_in"))
    )
  )
)
